# Lab03_Prelab.net
KiCad netlist of a schematic drawn in Altium Designer
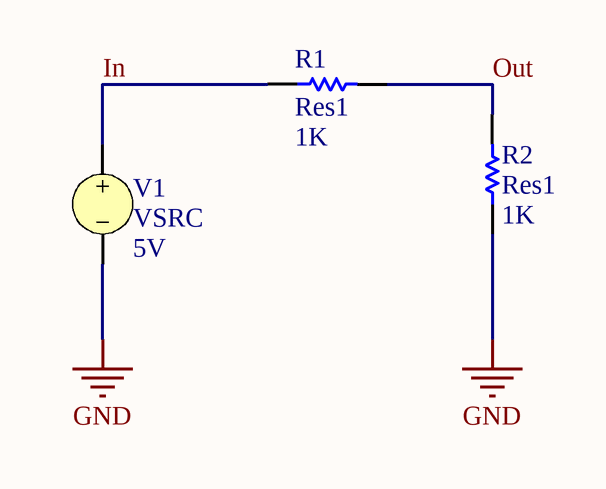
[diagram p0: Lab03_Prelab.SchDoc]

(export (version "E")
  (design (tool "Eeschema 10.0.6"))
  (components
    (comp (ref "R1")
      (value "Res1")
      (footprint "AXIAL-0.3")
      (description "Resistor")
      (fields (field (name "ALTIUM_VALUE") "1K") (field (name "PUBLISHER") "Altium Limited"))
      (libsource (lib "Miscellaneous Devices") (part "Res1"))
    )
    (comp (ref "R2")
      (value "Res1")
      (footprint "AXIAL-0.3")
      (description "Resistor")
      (fields (field (name "ALTIUM_VALUE") "1K") (field (name "PUBLISHER") "Altium Limited"))
      (libsource (lib "Miscellaneous Devices") (part "Res1"))
    )
    (comp (ref "V1")
      (value "VSRC")
      (description "Voltage Source")
      (fields (field (name "ALTIUM_VALUE") "5V") (field (name "PUBLISHER") "Altium Limited"))
      (libsource (lib "Simulation Sources") (part "VSRC"))
    )
  )
  (nets
    (net (code "1") (name "/In") (class "Default")
      (node (ref "R1") (pin "1") (pinfunction "1_1") (pintype "passive"))
      (node (ref "V1") (pin "1") (pinfunction "1_1") (pintype "passive"))
    )
    (net (code "2") (name "/Out") (class "Default")
      (node (ref "R1") (pin "2") (pinfunction "2_2") (pintype "passive"))
      (node (ref "R2") (pin "2") (pinfunction "2_2") (pintype "passive"))
    )
    (net (code "3") (name "GND") (class "Default")
      (node (ref "R2") (pin "1") (pinfunction "1_1") (pintype "passive"))
      (node (ref "V1") (pin "2") (pinfunction "2_2") (pintype "passive"))
    )
  )
)
